# USB.net
KiCad netlist of a schematic drawn in Altium Designer
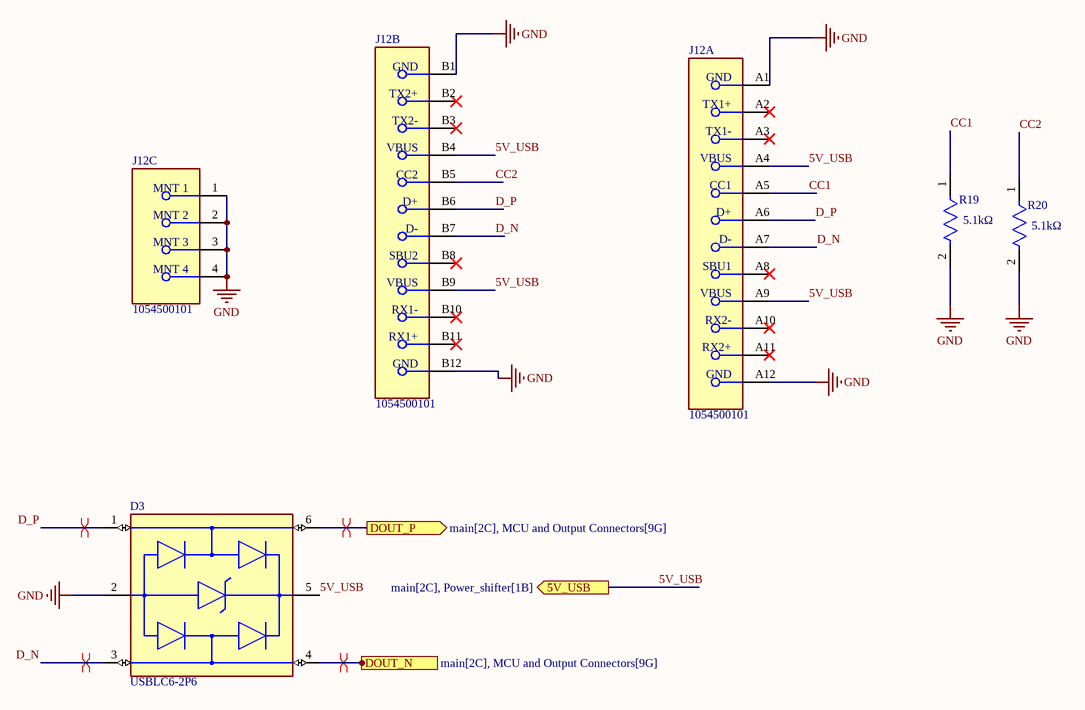
[diagram p0: USB.SchDoc]

(export (version "E")
  (design (tool "Eeschema 10.0.6"))
  (components
    (comp (ref "D3")
      (value "USBLC6-2P6")
      (footprint "FP-SOT-666-MFG")
      (description "TVS DIODE 5.25V 17V SOT666")
      (libsource (lib "Altium Content Vault") (part "c871e55f7e3243d341edbd671b98d92"))
    )
    (comp (ref "J12")
      (value "1054500101")
      (footprint "FP-1054500101-MFG")
      (description "CONN RCP USB3.1 TYPEC 24P SMD RA")
      (fields
        (field (name "MANUFACTURER") "Molex")
        (field (name "OCTOPART") "https://octopart.com/105450-0101-molex-68082325")
      )
      (libsource (lib "Altium Content Vault") (part "9808b19ecaf079fb99eed69f0495cd0"))
    )
    (comp (ref "R19")
      (value "MCWR04X5101FTL")
      (footprint "FP-MCWR04-IPC_C")
      (description "RES 5.1 kohm, 62.5 mW, 1%, 50 V")
      (fields
        (field (name "RESISTANCE") "5.1kΩ")
        (field (name "OCTOPART") "https://octopart.com/mcwr04x5101ftl-multicomp-50550258")
        (field (name "TOLERANCE") "1%")
      )
      (libsource (lib "Altium Content Vault") (part "1029c3af85768c4190bb7ad29bc67b5"))
    )
    (comp (ref "R20")
      (value "MCWR04X5101FTL")
      (footprint "FP-MCWR04-IPC_C")
      (description "RES 5.1 kohm, 62.5 mW, 1%, 50 V")
      (fields
        (field (name "RESISTANCE") "5.1kΩ")
        (field (name "OCTOPART") "https://octopart.com/mcwr04x5101ftl-multicomp-50550258")
        (field (name "TOLERANCE") "1%")
      )
      (libsource (lib "Altium Content Vault") (part "1029c3af85768c4190bb7ad29bc67b5"))
    )
  )
  (nets
    (net (code "1") (name "/5V_USB") (class "Default")
      (node (ref "D3") (pin "5") (pinfunction "VBUS_5") (pintype "power_in"))
      (node (ref "J12") (pin "A4") (pinfunction "VBUS_A4") (pintype "passive"))
      (node (ref "J12") (pin "A9") (pinfunction "VBUS_A9") (pintype "passive"))
      (node (ref "J12") (pin "B4") (pinfunction "VBUS_B4") (pintype "passive"))
      (node (ref "J12") (pin "B9") (pinfunction "VBUS_B9") (pintype "passive"))
    )
    (net (code "2") (name "/CC1") (class "Default")
      (node (ref "J12") (pin "A5") (pinfunction "CC1_A5") (pintype "passive"))
      (node (ref "R19") (pin "1") (pinfunction "1_1") (pintype "passive"))
    )
    (net (code "3") (name "/CC2") (class "Default")
      (node (ref "J12") (pin "B5") (pinfunction "CC2_B5") (pintype "passive"))
      (node (ref "R20") (pin "1") (pinfunction "1_1") (pintype "passive"))
    )
    (net (code "4") (name "/DOUT_N") (class "Default")
      (node (ref "D3") (pin "4") (pinfunction "I/O2_4") (pintype "bidirectional"))
    )
    (net (code "5") (name "/DOUT_P") (class "Default")
      (node (ref "D3") (pin "6") (pinfunction "I/O1_6") (pintype "bidirectional"))
    )
    (net (code "6") (name "/D_N") (class "Default")
      (node (ref "D3") (pin "3") (pinfunction "I/O2_3") (pintype "bidirectional"))
      (node (ref "J12") (pin "A7") (pinfunction "D-_A7") (pintype "passive"))
      (node (ref "J12") (pin "B7") (pinfunction "D-_B7") (pintype "passive"))
    )
    (net (code "7") (name "/D_P") (class "Default")
      (node (ref "D3") (pin "1") (pinfunction "I/O1_1") (pintype "bidirectional"))
      (node (ref "J12") (pin "A6") (pinfunction "D+_A6") (pintype "passive"))
      (node (ref "J12") (pin "B6") (pinfunction "D+_B6") (pintype "passive"))
    )
    (net (code "8") (name "GND") (class "Default")
      (node (ref "D3") (pin "2") (pinfunction "GND_2") (pintype "power_in"))
      (node (ref "J12") (pin "1") (pinfunction "MNT_1_1") (pintype "passive"))
      (node (ref "J12") (pin "2") (pinfunction "MNT_2_2") (pintype "passive"))
      (node (ref "J12") (pin "3") (pinfunction "MNT_3_3") (pintype "passive"))
      (node (ref "J12") (pin "4") (pinfunction "MNT_4_4") (pintype "passive"))
      (node (ref "J12") (pin "A1") (pinfunction "GND_A1") (pintype "passive"))
      (node (ref "J12") (pin "A12") (pinfunction "GND_A12") (pintype "passive"))
      (node (ref "J12") (pin "B1") (pinfunction "GND_B1") (pintype "passive"))
      (node (ref "J12") (pin "B12") (pinfunction "GND_B12") (pintype "passive"))
      (node (ref "R19") (pin "2") (pinfunction "2_2") (pintype "passive"))
      (node (ref "R20") (pin "2") (pinfunction "2_2") (pintype "passive"))
    )
    (net (code "9") (name "unconnected-(J12A-RX2+-PadA11)") (class "Default")
      (node (ref "J12") (pin "A11") (pinfunction "RX2+_A11") (pintype "passive+no_connect"))
    )
    (net (code "10") (name "unconnected-(J12A-RX2--PadA10)") (class "Default")
      (node (ref "J12") (pin "A10") (pinfunction "RX2-_A10") (pintype "passive+no_connect"))
    )
    (net (code "11") (name "unconnected-(J12A-SBU1-PadA8)") (class "Default")
      (node (ref "J12") (pin "A8") (pinfunction "SBU1_A8") (pintype "passive+no_connect"))
    )
    (net (code "12") (name "unconnected-(J12A-TX1+-PadA2)") (class "Default")
      (node (ref "J12") (pin "A2") (pinfunction "TX1+_A2") (pintype "passive+no_connect"))
    )
    (net (code "13") (name "unconnected-(J12A-TX1--PadA3)") (class "Default")
      (node (ref "J12") (pin "A3") (pinfunction "TX1-_A3") (pintype "passive+no_connect"))
    )
    (net (code "14") (name "unconnected-(J12B-RX1+-PadB11)") (class "Default")
      (node (ref "J12") (pin "B11") (pinfunction "RX1+_B11") (pintype "passive+no_connect"))
    )
    (net (code "15") (name "unconnected-(J12B-RX1--PadB10)") (class "Default")
      (node (ref "J12") (pin "B10") (pinfunction "RX1-_B10") (pintype "passive+no_connect"))
    )
    (net (code "16") (name "unconnected-(J12B-SBU2-PadB8)") (class "Default")
      (node (ref "J12") (pin "B8") (pinfunction "SBU2_B8") (pintype "passive+no_connect"))
    )
    (net (code "17") (name "unconnected-(J12B-TX2+-PadB2)") (class "Default")
      (node (ref "J12") (pin "B2") (pinfunction "TX2+_B2") (pintype "passive+no_connect"))
    )
    (net (code "18") (name "unconnected-(J12B-TX2--PadB3)") (class "Default")
      (node (ref "J12") (pin "B3") (pinfunction "TX2-_B3") (pintype "passive+no_connect"))
    )
  )
)
